# PGTN002.net
KiCad netlist of a schematic drawn in EAGLE
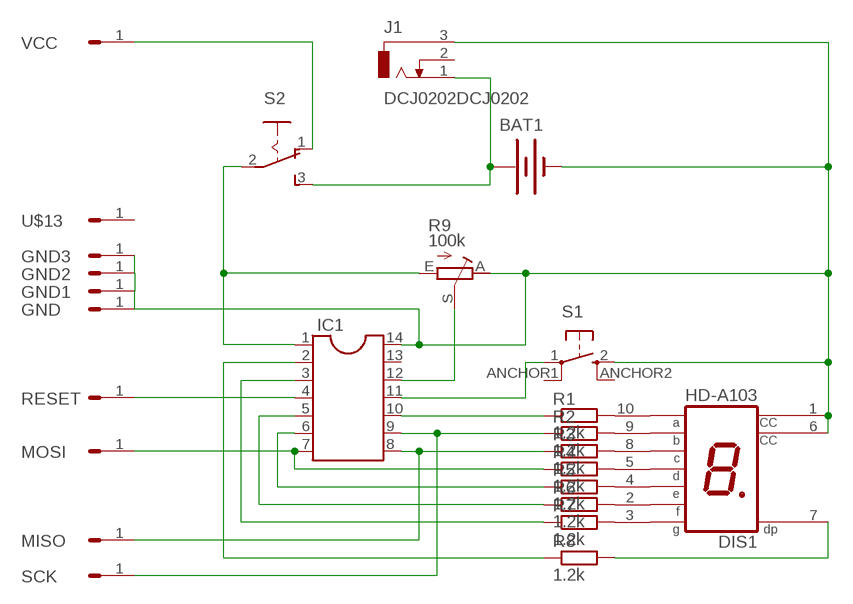
[diagram p0: schematic, sheet 1]

(export (version "E")
  (design (tool "Eeschema 10.0.6"))
  (components
    (comp (ref "BAT1")
      (value "BATTERY20PTH")
      (footprint "eagle-import:BATTCOM_20MM_PTH")
      (libsource (lib "eagle-import") (part "BATTERY20PTH"))
    )
    (comp (ref "DIS1")
      (value "HD-A103")
      (footprint "eagle-import:HDSP-A")
      (libsource (lib "eagle-import") (part "HD-A103"))
    )
    (comp (ref "GND")
      (value "HEADER/MALE/01")
      (footprint "eagle-import:HEADER_MALE_01")
      (libsource (lib "eagle-import") (part "HEADER/MALE/01"))
    )
    (comp (ref "GND1")
      (value "HEADER/MALE/01")
      (footprint "eagle-import:HEADER_MALE_01")
      (libsource (lib "eagle-import") (part "HEADER/MALE/01"))
    )
    (comp (ref "GND2")
      (value "HEADER/MALE/01")
      (footprint "eagle-import:HEADER_MALE_01")
      (libsource (lib "eagle-import") (part "HEADER/MALE/01"))
    )
    (comp (ref "GND3")
      (value "HEADER/MALE/01")
      (footprint "eagle-import:HEADER_MALE_01")
      (libsource (lib "eagle-import") (part "HEADER/MALE/01"))
    )
    (comp (ref "IC1")
      (value "DIL14S")
      (footprint "eagle-import:SOCKET-14")
      (libsource (lib "eagle-import") (part "DIL14S"))
    )
    (comp (ref "J1")
      (value "DCJ0202DCJ0202")
      (footprint "eagle-import:DCJ0202")
      (libsource (lib "eagle-import") (part "DCJ0202DCJ0202"))
    )
    (comp (ref "MISO")
      (value "HEADER/MALE/01")
      (footprint "eagle-import:HEADER_MALE_01")
      (libsource (lib "eagle-import") (part "HEADER/MALE/01"))
    )
    (comp (ref "MOSI")
      (value "HEADER/MALE/01")
      (footprint "eagle-import:HEADER_MALE_01")
      (libsource (lib "eagle-import") (part "HEADER/MALE/01"))
    )
    (comp (ref "R1")
      (value "1.2k")
      (footprint "eagle-import:RESISTOR_7.5")
      (libsource (lib "eagle-import") (part "RESISTORRESISTOR/UPRIGHT/7.5"))
    )
    (comp (ref "R2")
      (value "1.2k")
      (footprint "eagle-import:RESISTOR_7.5")
      (libsource (lib "eagle-import") (part "RESISTORRESISTOR/UPRIGHT/7.5"))
    )
    (comp (ref "R3")
      (value "1.2k")
      (footprint "eagle-import:RESISTOR_7.5")
      (libsource (lib "eagle-import") (part "RESISTORRESISTOR/UPRIGHT/7.5"))
    )
    (comp (ref "R4")
      (value "1.2k")
      (footprint "eagle-import:RESISTOR_7.5")
      (libsource (lib "eagle-import") (part "RESISTORRESISTOR/UPRIGHT/7.5"))
    )
    (comp (ref "R5")
      (value "1.2k")
      (footprint "eagle-import:RESISTOR_7.5")
      (libsource (lib "eagle-import") (part "RESISTORRESISTOR/UPRIGHT/7.5"))
    )
    (comp (ref "R6")
      (value "1.2k")
      (footprint "eagle-import:RESISTOR_7.5")
      (libsource (lib "eagle-import") (part "RESISTORRESISTOR/UPRIGHT/7.5"))
    )
    (comp (ref "R7")
      (value "1.2k")
      (footprint "eagle-import:RESISTOR_7.5")
      (libsource (lib "eagle-import") (part "RESISTORRESISTOR/UPRIGHT/7.5"))
    )
    (comp (ref "R8")
      (value "1.2k")
      (footprint "eagle-import:RESISTOR_7.5")
      (libsource (lib "eagle-import") (part "RESISTORRESISTOR/UPRIGHT/7.5"))
    )
    (comp (ref "R9")
      (value "100k")
      (footprint "eagle-import:TRIMMER_LI15")
      (libsource (lib "eagle-import") (part "TRIMMERPT15"))
    )
    (comp (ref "RESET")
      (value "HEADER/MALE/01")
      (footprint "eagle-import:HEADER_MALE_01")
      (libsource (lib "eagle-import") (part "HEADER/MALE/01"))
    )
    (comp (ref "S1")
      (value "SWITCH_TACTILE")
      (footprint "eagle-import:TACTILE-PTH-SIDEEZ")
      (libsource (lib "eagle-import") (part "SWITCH_TACTILE"))
    )
    (comp (ref "S2")
      (value "SWITCH_SLIDE")
      (footprint "eagle-import:SWITCH_SLIDE")
      (libsource (lib "eagle-import") (part "SWITCH_SLIDE"))
    )
    (comp (ref "SCK")
      (value "HEADER/MALE/01")
      (footprint "eagle-import:HEADER_MALE_01")
      (libsource (lib "eagle-import") (part "HEADER/MALE/01"))
    )
    (comp (ref "U$13")
      (value "HEADER/MALE/01")
      (footprint "eagle-import:HEADER_MALE_01")
      (libsource (lib "eagle-import") (part "HEADER/MALE/01"))
    )
    (comp (ref "VCC")
      (value "HEADER/MALE/01")
      (footprint "eagle-import:HEADER_MALE_01")
      (libsource (lib "eagle-import") (part "HEADER/MALE/01"))
    )
  )
  (nets
    (net (code "1") (name "Net-(BAT1-+)") (class "Default")
      (node (ref "BAT1") (pin "1") (pinfunction "+_1") (pintype "power_in"))
      (node (ref "J1") (pin "1") (pinfunction "3_1") (pintype "passive"))
      (node (ref "S2") (pin "3") (pinfunction "S_3") (pintype "passive"))
    )
    (net (code "2") (name "Net-(BAT1--)") (class "Default")
      (node (ref "BAT1") (pin "2") (pinfunction "-_2") (pintype "power_in"))
      (node (ref "DIS1") (pin "1") (pinfunction "CC_1") (pintype "passive"))
      (node (ref "DIS1") (pin "6") (pinfunction "CC_6") (pintype "passive"))
      (node (ref "GND") (pin "1") (pinfunction "3_1") (pintype "passive"))
      (node (ref "GND1") (pin "1") (pinfunction "3_1") (pintype "passive"))
      (node (ref "GND2") (pin "1") (pinfunction "3_1") (pintype "passive"))
      (node (ref "GND3") (pin "1") (pinfunction "3_1") (pintype "passive"))
      (node (ref "IC1") (pin "14") (pinfunction "14_14") (pintype "passive"))
      (node (ref "J1") (pin "3") (pinfunction "1_3") (pintype "passive"))
      (node (ref "R9") (pin "A") (pinfunction "A_A") (pintype "passive"))
      (node (ref "S1") (pin "2") (pinfunction "3_2") (pintype "passive"))
    )
    (net (code "3") (name "Net-(DIS1-A)") (class "Default")
      (node (ref "DIS1") (pin "10") (pinfunction "A_10") (pintype "passive"))
      (node (ref "R1") (pin "2") (pinfunction "2_2") (pintype "passive"))
    )
    (net (code "4") (name "Net-(DIS1-B)") (class "Default")
      (node (ref "DIS1") (pin "9") (pinfunction "B_9") (pintype "passive"))
      (node (ref "R2") (pin "2") (pinfunction "2_2") (pintype "passive"))
    )
    (net (code "5") (name "Net-(DIS1-C)") (class "Default")
      (node (ref "DIS1") (pin "8") (pinfunction "C_8") (pintype "passive"))
      (node (ref "R3") (pin "2") (pinfunction "2_2") (pintype "passive"))
    )
    (net (code "6") (name "Net-(DIS1-D)") (class "Default")
      (node (ref "DIS1") (pin "5") (pinfunction "D_5") (pintype "passive"))
      (node (ref "R4") (pin "2") (pinfunction "2_2") (pintype "passive"))
    )
    (net (code "7") (name "Net-(DIS1-DP)") (class "Default")
      (node (ref "DIS1") (pin "7") (pinfunction "DP_7") (pintype "passive"))
      (node (ref "R8") (pin "2") (pinfunction "2_2") (pintype "passive"))
    )
    (net (code "8") (name "Net-(DIS1-E)") (class "Default")
      (node (ref "DIS1") (pin "4") (pinfunction "E_4") (pintype "passive"))
      (node (ref "R5") (pin "2") (pinfunction "2_2") (pintype "passive"))
    )
    (net (code "9") (name "Net-(DIS1-F)") (class "Default")
      (node (ref "DIS1") (pin "2") (pinfunction "F_2") (pintype "passive"))
      (node (ref "R6") (pin "2") (pinfunction "2_2") (pintype "passive"))
    )
    (net (code "10") (name "Net-(DIS1-G)") (class "Default")
      (node (ref "DIS1") (pin "3") (pinfunction "G_3") (pintype "passive"))
      (node (ref "R7") (pin "2") (pinfunction "2_2") (pintype "passive"))
    )
    (net (code "11") (name "Net-(IC1-Pad2)") (class "Default")
      (node (ref "IC1") (pin "2") (pinfunction "2_2") (pintype "passive"))
      (node (ref "R8") (pin "1") (pinfunction "1_1") (pintype "passive"))
    )
    (net (code "12") (name "Net-(IC1-Pad3)") (class "Default")
      (node (ref "IC1") (pin "3") (pinfunction "3_3") (pintype "passive"))
      (node (ref "R7") (pin "1") (pinfunction "1_1") (pintype "passive"))
    )
    (net (code "13") (name "Net-(IC1-Pad5)") (class "Default")
      (node (ref "IC1") (pin "5") (pinfunction "5_5") (pintype "passive"))
      (node (ref "R6") (pin "1") (pinfunction "1_1") (pintype "passive"))
    )
    (net (code "14") (name "Net-(IC1-Pad6)") (class "Default")
      (node (ref "IC1") (pin "6") (pinfunction "6_6") (pintype "passive"))
      (node (ref "R5") (pin "1") (pinfunction "1_1") (pintype "passive"))
    )
    (net (code "15") (name "Net-(IC1-Pad10)") (class "Default")
      (node (ref "IC1") (pin "10") (pinfunction "10_10") (pintype "passive"))
      (node (ref "R1") (pin "1") (pinfunction "1_1") (pintype "passive"))
    )
    (net (code "16") (name "Net-(IC1-Pad11)") (class "Default")
      (node (ref "IC1") (pin "11") (pinfunction "11_11") (pintype "passive"))
      (node (ref "S1") (pin "1") (pinfunction "1_1") (pintype "passive"))
    )
    (net (code "17") (name "Net-(IC1-Pad12)") (class "Default")
      (node (ref "IC1") (pin "12") (pinfunction "12_12") (pintype "passive"))
      (node (ref "R9") (pin "S") (pinfunction "S_S") (pintype "passive"))
    )
    (net (code "18") (name "Net-(MISO-3)") (class "Default")
      (node (ref "IC1") (pin "8") (pinfunction "8_8") (pintype "passive"))
      (node (ref "MISO") (pin "1") (pinfunction "3_1") (pintype "passive"))
      (node (ref "R3") (pin "1") (pinfunction "1_1") (pintype "passive"))
    )
    (net (code "19") (name "Net-(MOSI-3)") (class "Default")
      (node (ref "IC1") (pin "7") (pinfunction "7_7") (pintype "passive"))
      (node (ref "MOSI") (pin "1") (pinfunction "3_1") (pintype "passive"))
      (node (ref "R4") (pin "1") (pinfunction "1_1") (pintype "passive"))
    )
    (net (code "20") (name "Net-(RESET-3)") (class "Default")
      (node (ref "IC1") (pin "4") (pinfunction "4_4") (pintype "passive"))
      (node (ref "RESET") (pin "1") (pinfunction "3_1") (pintype "passive"))
    )
    (net (code "21") (name "Net-(S2-O)") (class "Default")
      (node (ref "S2") (pin "1") (pinfunction "O_1") (pintype "passive"))
      (node (ref "VCC") (pin "1") (pinfunction "3_1") (pintype "passive"))
    )
    (net (code "22") (name "Net-(S2-P)") (class "Default")
      (node (ref "IC1") (pin "1") (pinfunction "1_1") (pintype "passive"))
      (node (ref "R9") (pin "E") (pinfunction "E_E") (pintype "passive"))
      (node (ref "S2") (pin "2") (pinfunction "P_2") (pintype "passive"))
    )
    (net (code "23") (name "Net-(SCK-3)") (class "Default")
      (node (ref "IC1") (pin "9") (pinfunction "9_9") (pintype "passive"))
      (node (ref "R2") (pin "1") (pinfunction "1_1") (pintype "passive"))
      (node (ref "SCK") (pin "1") (pinfunction "3_1") (pintype "passive"))
    )
    (net (code "24") (name "unconnected-(IC1-Pad13)") (class "Default")
      (node (ref "IC1") (pin "13") (pinfunction "13_13") (pintype "passive"))
    )
    (net (code "25") (name "unconnected-(J1-Pad2)") (class "Default")
      (node (ref "J1") (pin "2") (pinfunction "2_2") (pintype "passive"))
    )
    (net (code "26") (name "unconnected-(S1-2-PadANCHOR1)") (class "Default")
      (node (ref "S1") (pin "ANCHOR1") (pinfunction "2_ANCHOR1") (pintype "passive"))
    )
    (net (code "27") (name "unconnected-(S1-4-PadANCHOR2)") (class "Default")
      (node (ref "S1") (pin "ANCHOR2") (pinfunction "4_ANCHOR2") (pintype "passive"))
    )
    (net (code "28") (name "unconnected-(U$13-3-Pad1)") (class "Default")
      (node (ref "U$13") (pin "1") (pinfunction "3_1") (pintype "passive"))
    )
  )
)
